# controller.net
KiCad netlist of a schematic drawn in EAGLE
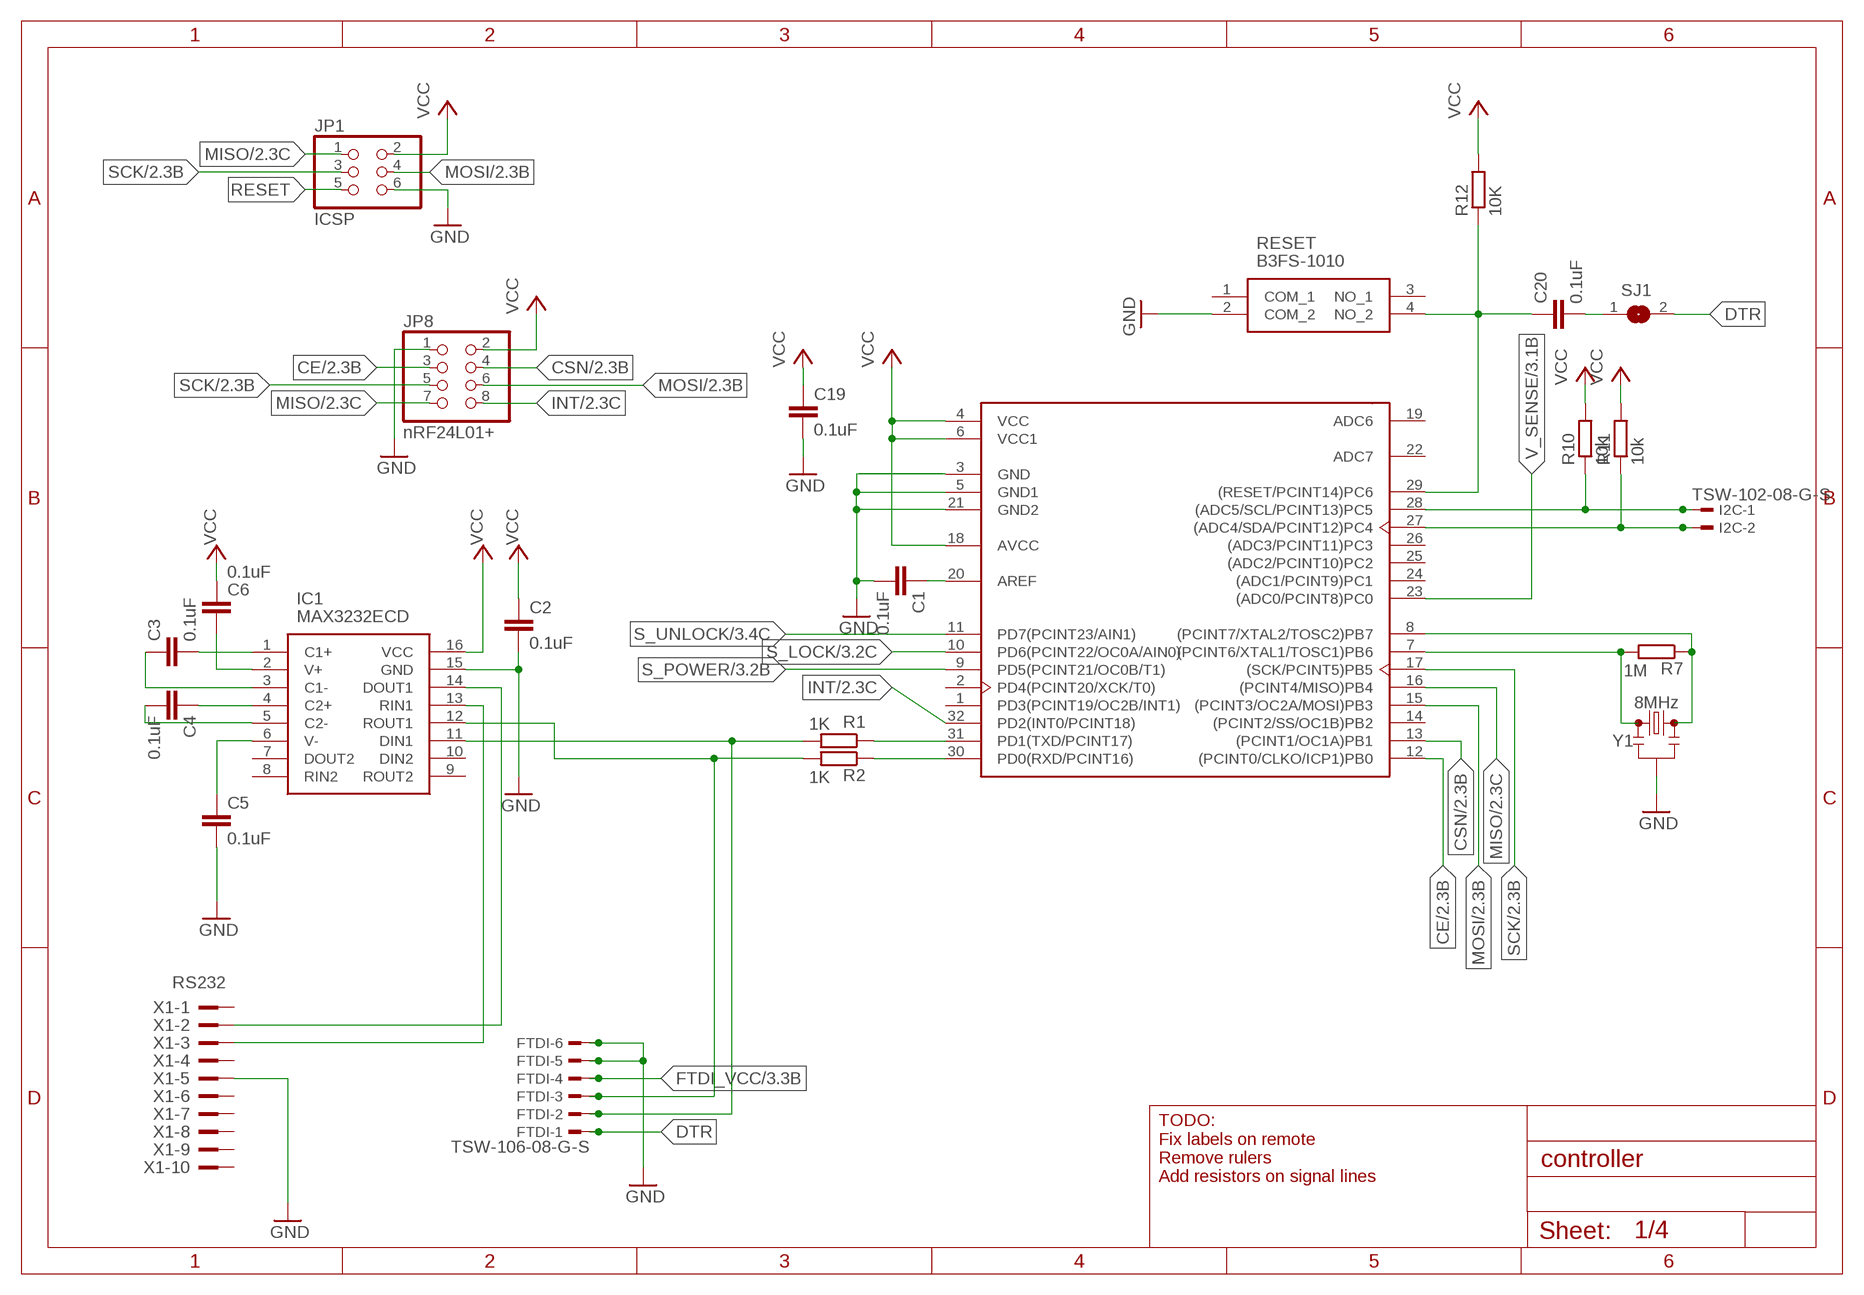
[diagram p0: schematic, sheet 1]
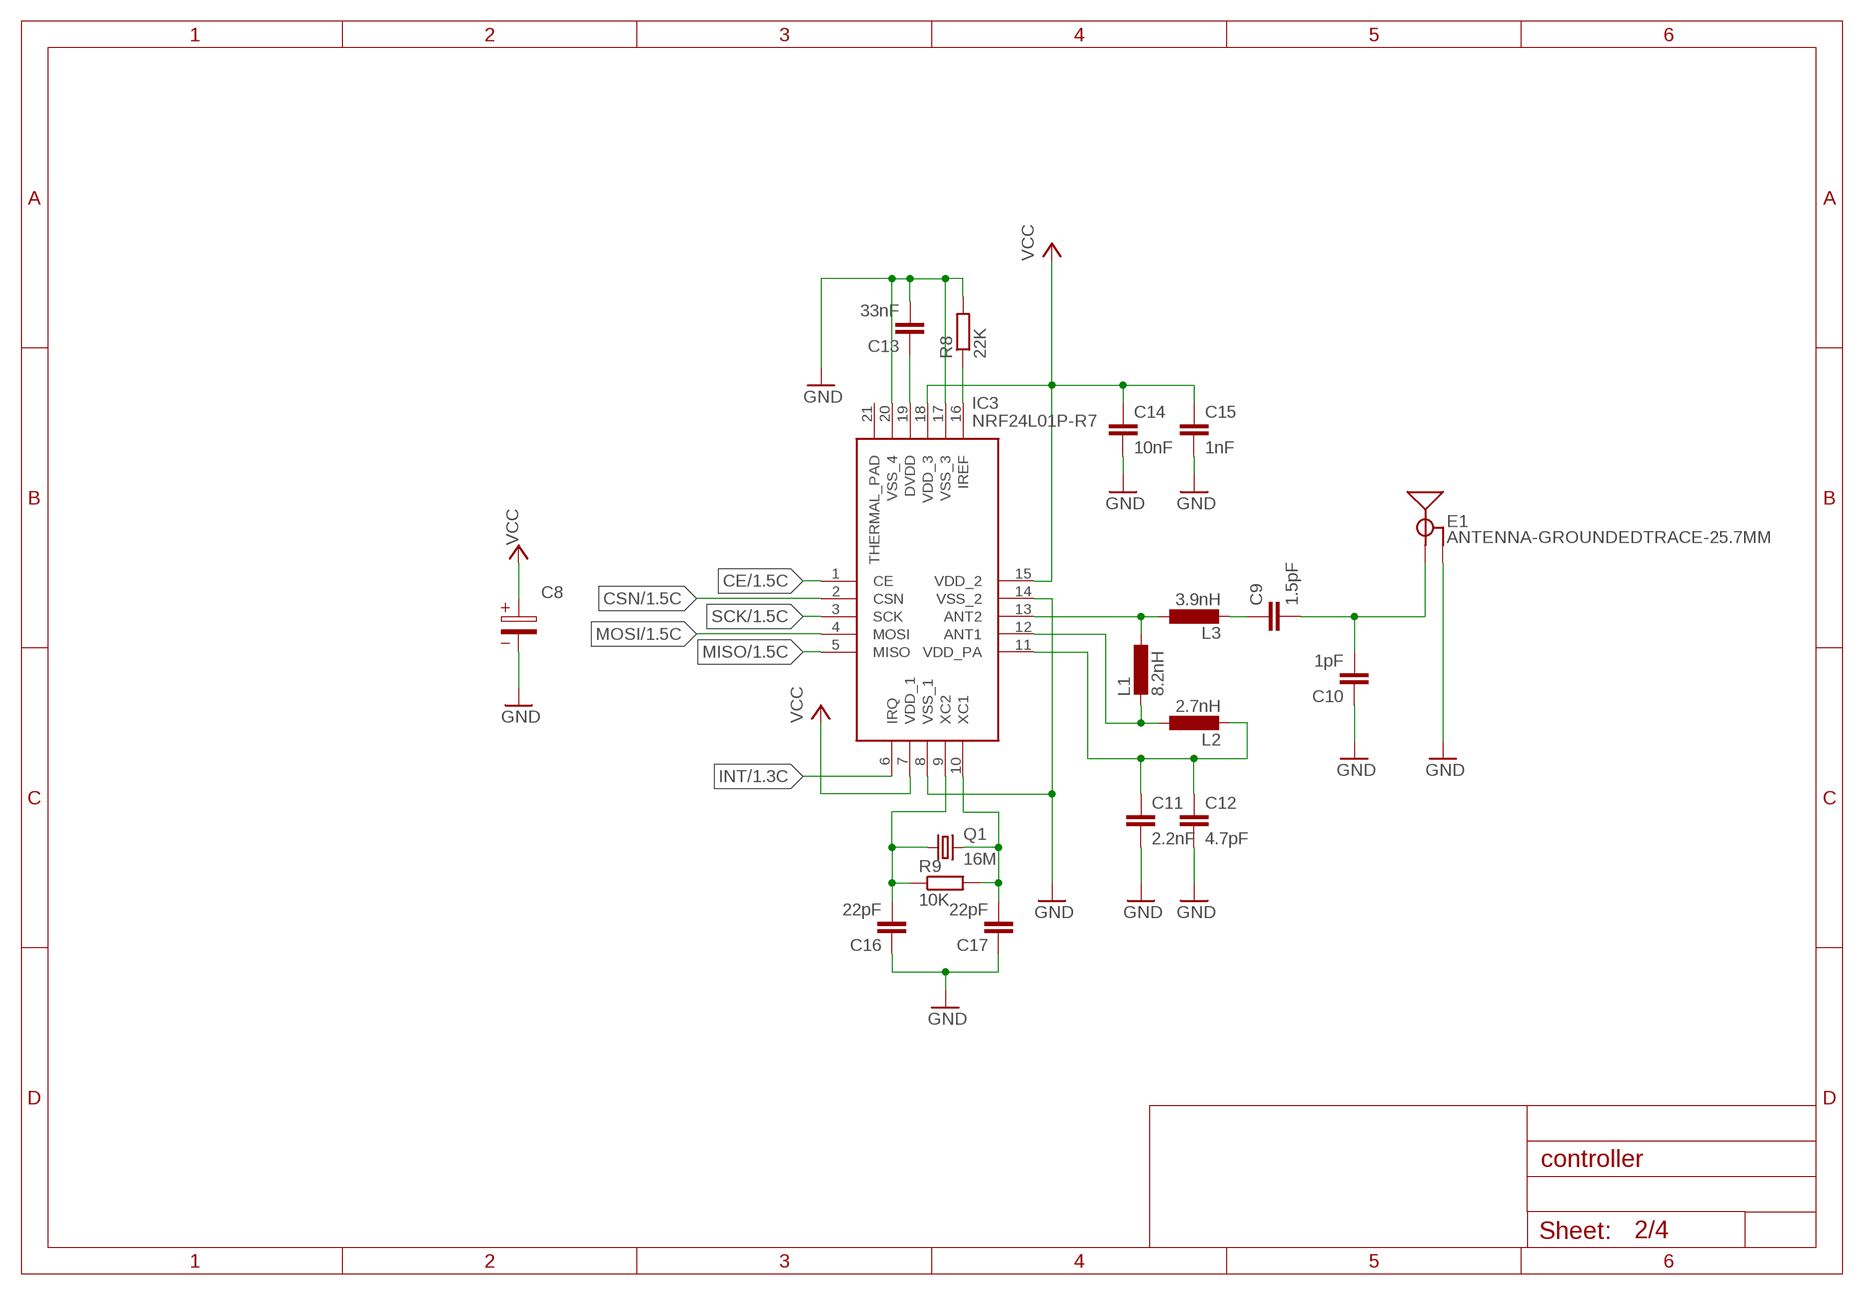
[diagram p1: schematic, sheet 2]
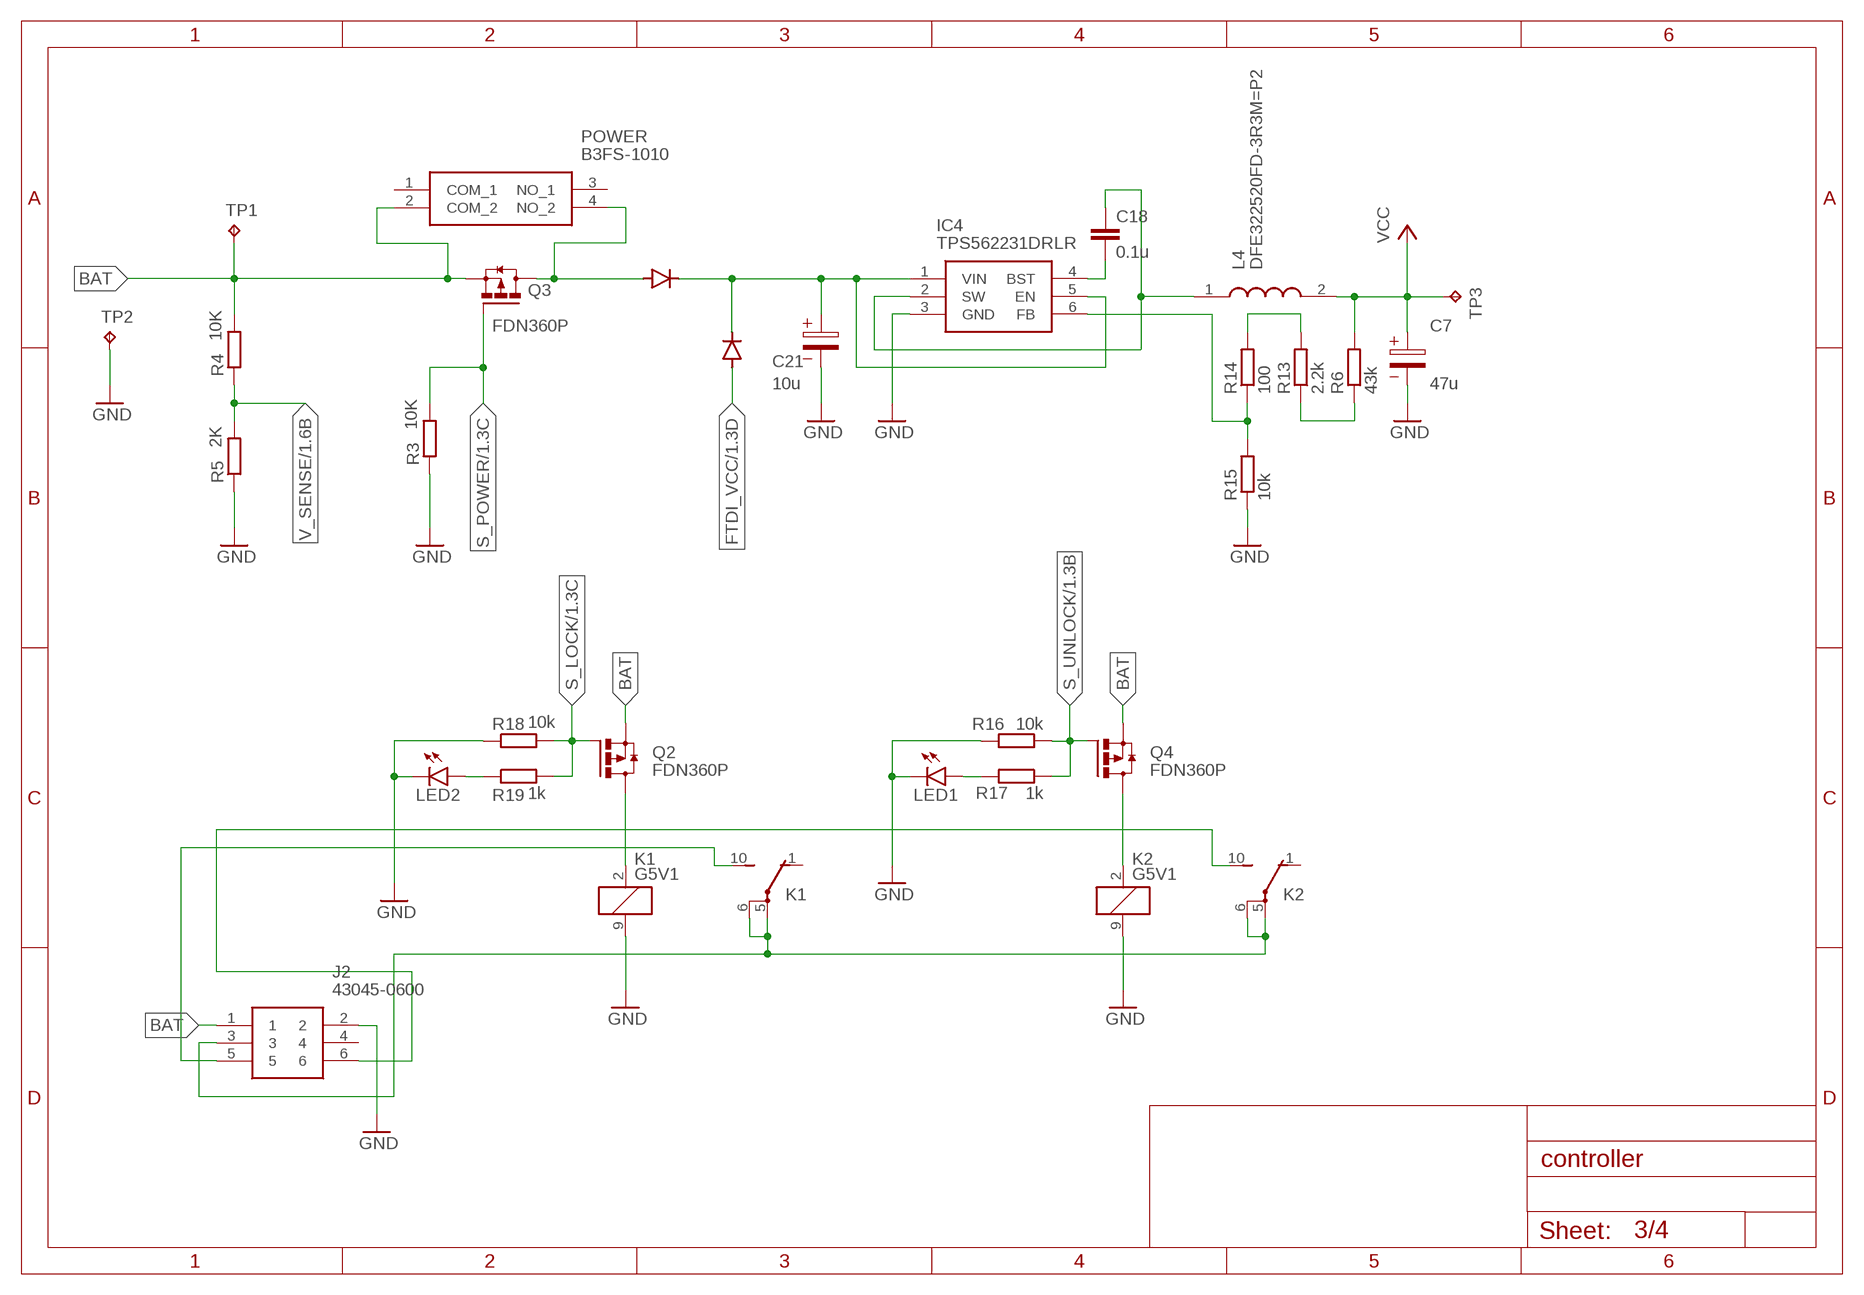
[diagram p2: schematic, sheet 3]
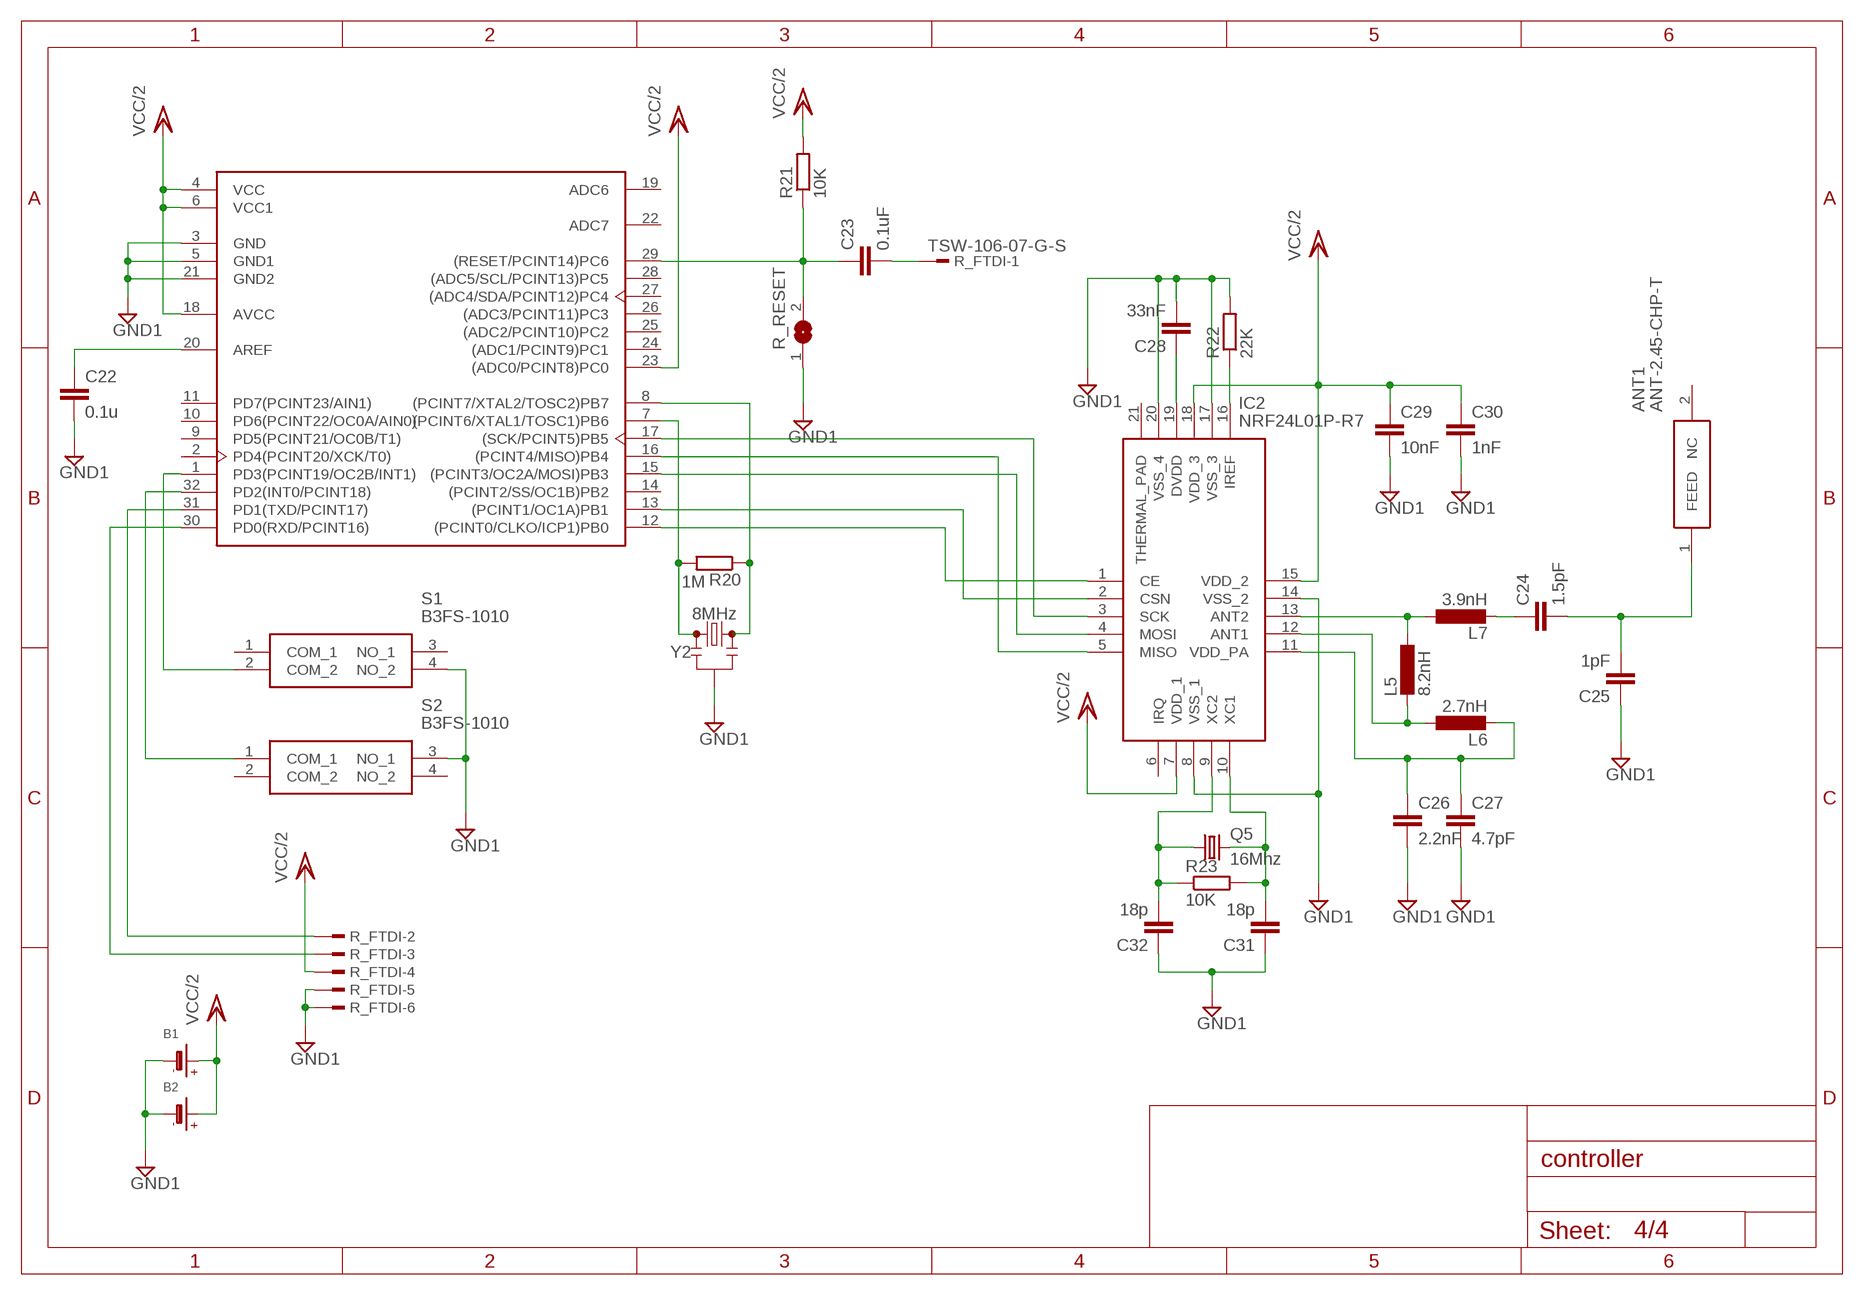
[diagram p3: schematic, sheet 4]

(export (version "E")
  (design (tool "Eeschema 10.0.6"))
  (components
    (comp (ref "C8")
      (value "WCAP-ASLI_8X6,5_865080149011")
      (footprint "eagle-import:4.2X1.9X2.8(BXCXA)")
      (libsource (lib "eagle-import") (part "WCAP-ASLI_865080149011_8X6,5"))
    )
    (comp (ref "C9")
      (value "1.5pF")
      (footprint "eagle-import:C0805")
      (libsource (lib "eagle-import") (part "resistor_348_C-EUC0805"))
    )
    (comp (ref "C10")
      (value "1pF")
      (footprint "eagle-import:C0805")
      (libsource (lib "eagle-import") (part "resistor_348_C-EUC0805"))
    )
    (comp (ref "C11")
      (value "2.2nF")
      (footprint "eagle-import:C0805")
      (libsource (lib "eagle-import") (part "resistor_348_C-EUC0805"))
    )
    (comp (ref "C12")
      (value "4.7pF")
      (footprint "eagle-import:C0805")
      (libsource (lib "eagle-import") (part "resistor_348_C-EUC0805"))
    )
    (comp (ref "C13")
      (value "33nF")
      (footprint "eagle-import:C0805")
      (libsource (lib "eagle-import") (part "resistor_348_C-EUC0805"))
    )
    (comp (ref "C14")
      (value "10nF")
      (footprint "eagle-import:C0805")
      (libsource (lib "eagle-import") (part "resistor_348_C-EUC0805"))
    )
    (comp (ref "C15")
      (value "1nF")
      (footprint "eagle-import:C0805")
      (libsource (lib "eagle-import") (part "resistor_348_C-EUC0805"))
    )
    (comp (ref "C16")
      (value "22pF")
      (footprint "eagle-import:C0805")
      (libsource (lib "eagle-import") (part "resistor_348_C-EUC0805"))
    )
    (comp (ref "C17")
      (value "22pF")
      (footprint "eagle-import:C0805")
      (libsource (lib "eagle-import") (part "resistor_348_C-EUC0805"))
    )
    (comp (ref "E1")
      (value "ANTENNA-GROUNDEDTRACE-25.7MM")
      (footprint "eagle-import:TRACE_ANTENNA_2.4GHZ_25.7MM")
      (libsource (lib "eagle-import") (part "ANTENNA-GROUNDEDTRACE-25.7MM"))
    )
    (comp (ref "IC3")
      (value "NRF24L01P-R7")
      (footprint "eagle-import:QFN50P400X400X95-21N")
      (fields (field (name "MOUSER_PART_NUMBER") "949-NRF24L01P-R7"))
      (libsource (lib "eagle-import") (part "NRF24L01P-R7"))
    )
    (comp (ref "L1")
      (value "8.2nH")
      (footprint "eagle-import:L2012C")
      (libsource (lib "eagle-import") (part "L-EUL2012C"))
    )
    (comp (ref "L2")
      (value "2.7nH")
      (footprint "eagle-import:L2012C")
      (libsource (lib "eagle-import") (part "L-EUL2012C"))
    )
    (comp (ref "L3")
      (value "3.9nH")
      (footprint "eagle-import:L2012C")
      (libsource (lib "eagle-import") (part "L-EUL2012C"))
    )
    (comp (ref "Q1")
      (value "16M")
      (footprint "eagle-import:HC49_S")
      (libsource (lib "eagle-import") (part "CRYSTALHC49S"))
    )
    (comp (ref "R8")
      (value "22K")
      (footprint "eagle-import:R0805")
      (libsource (lib "eagle-import") (part "R-EU_R0805"))
    )
    (comp (ref "R9")
      (value "10K")
      (footprint "eagle-import:R0805")
      (libsource (lib "eagle-import") (part "R-EU_R0805"))
    )
    (comp (ref "C1")
      (value "0.1uF")
      (footprint "eagle-import:C0805")
      (libsource (lib "eagle-import") (part "C-EUC0805"))
    )
    (comp (ref "C2")
      (value "0.1uF")
      (footprint "eagle-import:C0805")
      (libsource (lib "eagle-import") (part "C-EUC0805"))
    )
    (comp (ref "C3")
      (value "0.1uF")
      (footprint "eagle-import:C0805")
      (libsource (lib "eagle-import") (part "C-EUC0805"))
    )
    (comp (ref "C4")
      (value "0.1uF")
      (footprint "eagle-import:C0805")
      (libsource (lib "eagle-import") (part "C-EUC0805"))
    )
    (comp (ref "C5")
      (value "0.1uF")
      (footprint "eagle-import:C0805")
      (libsource (lib "eagle-import") (part "C-EUC0805"))
    )
    (comp (ref "C6")
      (value "0.1uF")
      (footprint "eagle-import:C0805")
      (libsource (lib "eagle-import") (part "C-EUC0805"))
    )
    (comp (ref "C19")
      (value "0.1uF")
      (footprint "eagle-import:C0805")
      (libsource (lib "eagle-import") (part "C-EUC0805"))
    )
    (comp (ref "C20")
      (value "0.1uF")
      (footprint "eagle-import:C0805")
      (libsource (lib "eagle-import") (part "C-EUC0805"))
    )
    (comp (ref "FTDI")
      (value "TSW-106-08-G-S")
      (footprint "eagle-import:TSW-106-XX-G-S")
      (fields (field (name "MF") "Samtec Inc.") (field (name "MPN") "TSW-106-07-G-S"))
      (libsource (lib "eagle-import") (part "TSW-106--G-S08"))
    )
    (comp (ref "I2C")
      (value "TSW-102-08-G-S")
      (footprint "eagle-import:TSW-102-XX-G-S")
      (fields (field (name "MF") "Samtec Inc.") (field (name "MPN") "TSW-102-07-G-S"))
      (libsource (lib "eagle-import") (part "TSW-102--G-S08"))
    )
    (comp (ref "IC1")
      (value "MAX3232ECD")
      (footprint "eagle-import:SOIC127P600X175-16N")
      (fields (field (name "MOUSER_PART_NUMBER") "595-MAX3232ECD") (field (name "RS_PART_NUMBER") "6608704P"))
      (libsource (lib "eagle-import") (part "MAX3232ECD"))
    )
    (comp (ref "JP1")
      (value "ICSP")
      (footprint "eagle-import:2X03")
      (libsource (lib "eagle-import") (part "PINHD-2X3"))
    )
    (comp (ref "JP8")
      (value "nRF24L01+")
      (footprint "eagle-import:2X04")
      (libsource (lib "eagle-import") (part "PINHD-2X4"))
    )
    (comp (ref "R1")
      (value "1K")
      (footprint "eagle-import:R0805")
      (libsource (lib "eagle-import") (part "R-EU_R0805"))
    )
    (comp (ref "R2")
      (value "1K")
      (footprint "eagle-import:R0805")
      (libsource (lib "eagle-import") (part "R-EU_R0805"))
    )
    (comp (ref "R7")
      (value "1M")
      (footprint "eagle-import:R0805")
      (libsource (lib "eagle-import") (part "R-EU_R0805"))
    )
    (comp (ref "R10")
      (value "10k")
      (footprint "eagle-import:R0805")
      (libsource (lib "eagle-import") (part "R-EU_R0805"))
    )
    (comp (ref "R11")
      (value "10k")
      (footprint "eagle-import:R0805")
      (libsource (lib "eagle-import") (part "R-EU_R0805"))
    )
    (comp (ref "R12")
      (value "10K")
      (footprint "eagle-import:R0805")
      (libsource (lib "eagle-import") (part "R-EU_R0805"))
    )
    (comp (ref "RESET")
      (value "B3FS-1010")
      (footprint "eagle-import:B3FS-1000P")
      (fields (field (name "MOUSER_PART_NUMBER") "653-B3FS-1010") (field (name "RS_PART_NUMBER") "6821266P"))
      (libsource (lib "eagle-import") (part "B3FS-1010"))
    )
    (comp (ref "SJ1") (value "SJ") (footprint "eagle-import:SJ") (libsource (lib "eagle-import") (part "SJ")))
    (comp (ref "U2")
      (value "ATMEGA328P-AU")
      (footprint "eagle-import:TQFP-32")
      (fields
        (field (name "DIGIKEY_PART_NUMBER") "ATMEGA328P-AU-ND")
        (field (name "MANUFACTURER") "Microchip Technology")
        (field (name "CREATED_BY") "PCBLayout.com")
      )
      (libsource (lib "eagle-import") (part "ATMEGA328P-AU"))
    )
    (comp (ref "X1")
      (value "RS232")
      (footprint "eagle-import:PAK100_2500-10")
      (fields (field (name "MF") "3M") (field (name "MPN") "2510-6002UB"))
      (libsource (lib "eagle-import") (part "2510-"))
    )
    (comp (ref "Y1")
      (value "8MHz")
      (footprint "eagle-import:RESONATOR-SMD-3.2X1.3")
      (libsource (lib "eagle-import") (part "RESONATOR-8MHZSMD_3.2X1.3"))
    )
    (comp (ref "C7")
      (value "47u")
      (footprint "eagle-import:2.6X1.6X1(BXCXA)")
      (libsource (lib "eagle-import") (part "WCAP-ASLI_865080140004_4X5,5"))
    )
    (comp (ref "C18")
      (value "0.1u")
      (footprint "eagle-import:C0805")
      (libsource (lib "eagle-import") (part "C-EUC0805"))
    )
    (comp (ref "C21")
      (value "10u")
      (footprint "eagle-import:2.6X1.6X1(BXCXA)")
      (libsource (lib "eagle-import") (part "WCAP-ASLI_865080340001_4X5,5"))
    )
    (comp (ref "D1")
      (value "DIODE-SOD123")
      (footprint "eagle-import:SOD123")
      (libsource (lib "eagle-import") (part "DIODE-SOD123"))
    )
    (comp (ref "D2")
      (value "DIODE-SOD123")
      (footprint "eagle-import:SOD123")
      (libsource (lib "eagle-import") (part "DIODE-SOD123"))
    )
    (comp (ref "IC4")
      (value "TPS562231DRLR")
      (footprint "eagle-import:SOTFL50P160X60-6N")
      (fields (field (name "MOUSER_PART_NUMBER") "595-TPS562231DRLR"))
      (libsource (lib "eagle-import") (part "TPS562231DRLR"))
    )
    (comp (ref "J2")
      (value "43045-0600")
      (footprint "eagle-import:43045-0600")
      (fields (field (name "MOUSER_PART_NUMBER") "538-43045-0600") (field (name "RS_PART_NUMBER") "2332961P"))
      (libsource (lib "eagle-import") (part "43045-0600"))
    )
    (comp (ref "K1")
      (value "G5V1")
      (footprint "eagle-import:G5V1")
      (fields (field (name "MPN") "G5V-1-DC24"))
      (libsource (lib "eagle-import") (part "G5V1"))
    )
    (comp (ref "K2")
      (value "G5V1")
      (footprint "eagle-import:G5V1")
      (fields (field (name "MPN") "G5V-1-DC24"))
      (libsource (lib "eagle-import") (part "G5V1"))
    )
    (comp (ref "L4")
      (value "DFE322520FD-3R3M=P2")
      (footprint "eagle-import:INDC3225X200N")
      (fields (field (name "MOUSER_PART_NUMBER") "81-DFE322520FD3R3MP2"))
      (libsource (lib "eagle-import") (part "DFE322520FD-3R3M=P2"))
    )
    (comp (ref "LED1")
      (value "LEDCHIPLED_0805")
      (footprint "eagle-import:CHIPLED_0805")
      (libsource (lib "eagle-import") (part "LEDCHIPLED_0805"))
    )
    (comp (ref "LED2")
      (value "LEDCHIPLED_0805")
      (footprint "eagle-import:CHIPLED_0805")
      (libsource (lib "eagle-import") (part "LEDCHIPLED_0805"))
    )
    (comp (ref "POWER")
      (value "B3FS-1010")
      (footprint "eagle-import:B3FS-1000P")
      (fields (field (name "MOUSER_PART_NUMBER") "653-B3FS-1010") (field (name "RS_PART_NUMBER") "6821266P"))
      (libsource (lib "eagle-import") (part "B3FS-1010"))
    )
    (comp (ref "Q2")
      (value "FDN360P")
      (footprint "eagle-import:SUPER-SOT3")
      (libsource (lib "eagle-import") (part "FDN360P"))
    )
    (comp (ref "Q3")
      (value "FDN360P")
      (footprint "eagle-import:SUPER-SOT3")
      (libsource (lib "eagle-import") (part "FDN360P"))
    )
    (comp (ref "Q4")
      (value "FDN360P")
      (footprint "eagle-import:SUPER-SOT3")
      (libsource (lib "eagle-import") (part "FDN360P"))
    )
    (comp (ref "R3")
      (value "10K")
      (footprint "eagle-import:R0805")
      (libsource (lib "eagle-import") (part "R-EU_R0805"))
    )
    (comp (ref "R4")
      (value "10K")
      (footprint "eagle-import:R0805")
      (libsource (lib "eagle-import") (part "R-EU_R0805"))
    )
    (comp (ref "R5")
      (value "2K")
      (footprint "eagle-import:R0805")
      (libsource (lib "eagle-import") (part "R-EU_R0805"))
    )
    (comp (ref "R6")
      (value "43k")
      (footprint "eagle-import:R0805")
      (libsource (lib "eagle-import") (part "R-EU_R0805"))
    )
    (comp (ref "R13")
      (value "2.2k")
      (footprint "eagle-import:R0805")
      (libsource (lib "eagle-import") (part "R-EU_R0805"))
    )
    (comp (ref "R14")
      (value "100")
      (footprint "eagle-import:R0805")
      (libsource (lib "eagle-import") (part "R-EU_R0805"))
    )
    (comp (ref "R15")
      (value "10k")
      (footprint "eagle-import:R0805")
      (libsource (lib "eagle-import") (part "R-EU_R0805"))
    )
    (comp (ref "R16")
      (value "10k")
      (footprint "eagle-import:R0805")
      (libsource (lib "eagle-import") (part "R-EU_R0805"))
    )
    (comp (ref "R17")
      (value "1k")
      (footprint "eagle-import:R0805")
      (libsource (lib "eagle-import") (part "R-EU_R0805"))
    )
    (comp (ref "R18")
      (value "10k")
      (footprint "eagle-import:R0805")
      (libsource (lib "eagle-import") (part "R-EU_R0805"))
    )
    (comp (ref "R19")
      (value "1k")
      (footprint "eagle-import:R0805")
      (libsource (lib "eagle-import") (part "R-EU_R0805"))
    )
    (comp (ref "TP1")
      (value "TPB1,27")
      (footprint "eagle-import:B1,27")
      (libsource (lib "eagle-import") (part "TPB1,27"))
    )
    (comp (ref "TP2")
      (value "TPB1,27")
      (footprint "eagle-import:B1,27")
      (libsource (lib "eagle-import") (part "TPB1,27"))
    )
    (comp (ref "TP3")
      (value "TPB1,27")
      (footprint "eagle-import:B1,27")
      (libsource (lib "eagle-import") (part "TPB1,27"))
    )
    (comp (ref "ANT1")
      (value "ANT-2.45-CHP-T")
      (footprint "eagle-import:ANT-2.45-CHP-T")
      (fields (field (name "MOUSER_PART_NUMBER") "712-ANT-2.45-CHP-T"))
      (libsource (lib "eagle-import") (part "ANT-2.45-CHP-T"))
    )
    (comp (ref "B1")
      (value "BATTERYCR2032_BAT-HLD-001")
      (footprint "eagle-import:CR2032_SMT_BAT-HLD-001")
      (libsource (lib "eagle-import") (part "BATTERYCR2032_BAT-HLD-001"))
    )
    (comp (ref "B2")
      (value "BATTERYCR2032_BAT-HLD-001")
      (footprint "eagle-import:CR2032_SMT_BAT-HLD-001")
      (libsource (lib "eagle-import") (part "BATTERYCR2032_BAT-HLD-001"))
    )
    (comp (ref "C22")
      (value "0.1u")
      (footprint "eagle-import:C0805")
      (libsource (lib "eagle-import") (part "C-EUC0805"))
    )
    (comp (ref "C23")
      (value "0.1uF")
      (footprint "eagle-import:C0805")
      (libsource (lib "eagle-import") (part "C-EUC0805"))
    )
    (comp (ref "C24")
      (value "1.5pF")
      (footprint "eagle-import:C0805")
      (libsource (lib "eagle-import") (part "resistor_348_C-EUC0805"))
    )
    (comp (ref "C25")
      (value "1pF")
      (footprint "eagle-import:C0805")
      (libsource (lib "eagle-import") (part "resistor_348_C-EUC0805"))
    )
    (comp (ref "C26")
      (value "2.2nF")
      (footprint "eagle-import:C0805")
      (libsource (lib "eagle-import") (part "resistor_348_C-EUC0805"))
    )
    (comp (ref "C27")
      (value "4.7pF")
      (footprint "eagle-import:C0805")
      (libsource (lib "eagle-import") (part "resistor_348_C-EUC0805"))
    )
    (comp (ref "C28")
      (value "33nF")
      (footprint "eagle-import:C0805")
      (libsource (lib "eagle-import") (part "resistor_348_C-EUC0805"))
    )
    (comp (ref "C29")
      (value "10nF")
      (footprint "eagle-import:C0805")
      (libsource (lib "eagle-import") (part "resistor_348_C-EUC0805"))
    )
    (comp (ref "C30")
      (value "1nF")
      (footprint "eagle-import:C0805")
      (libsource (lib "eagle-import") (part "resistor_348_C-EUC0805"))
    )
    (comp (ref "C31")
      (value "18p")
      (footprint "eagle-import:C0805")
      (libsource (lib "eagle-import") (part "resistor_348_C-EUC0805"))
    )
    (comp (ref "C32")
      (value "18p")
      (footprint "eagle-import:C0805")
      (libsource (lib "eagle-import") (part "resistor_348_C-EUC0805"))
    )
    (comp (ref "IC2")
      (value "NRF24L01P-R7")
      (footprint "eagle-import:QFN50P400X400X95-21N")
      (fields (field (name "MOUSER_PART_NUMBER") "949-NRF24L01P-R7"))
      (libsource (lib "eagle-import") (part "NRF24L01P-R7"))
    )
    (comp (ref "L5")
      (value "8.2nH")
      (footprint "eagle-import:L2012C")
      (libsource (lib "eagle-import") (part "L-EUL2012C"))
    )
    (comp (ref "L6")
      (value "2.7nH")
      (footprint "eagle-import:L2012C")
      (libsource (lib "eagle-import") (part "L-EUL2012C"))
    )
    (comp (ref "L7")
      (value "3.9nH")
      (footprint "eagle-import:L2012C")
      (libsource (lib "eagle-import") (part "L-EUL2012C"))
    )
    (comp (ref "Q5")
      (value "16Mhz")
      (footprint "eagle-import:HC49UP")
      (libsource (lib "eagle-import") (part "CRYSTALHC49UP"))
    )
    (comp (ref "R20")
      (value "1M")
      (footprint "eagle-import:R0805")
      (libsource (lib "eagle-import") (part "R-EU_R0805"))
    )
    (comp (ref "R21")
      (value "10K")
      (footprint "eagle-import:R0805")
      (libsource (lib "eagle-import") (part "R-EU_R0805"))
    )
    (comp (ref "R22")
      (value "22K")
      (footprint "eagle-import:R0805")
      (libsource (lib "eagle-import") (part "R-EU_R0805"))
    )
    (comp (ref "R23")
      (value "10K")
      (footprint "eagle-import:R0805")
      (libsource (lib "eagle-import") (part "R-EU_R0805"))
    )
    (comp (ref "R_FTDI")
      (value "TSW-106-07-G-S")
      (footprint "eagle-import:TSW-106-XX-G-S")
      (fields (field (name "MF") "Samtec Inc."))
      (libsource (lib "eagle-import") (part "TSW-106--G-S07"))
    )
    (comp (ref "R_RESET")
      (value "SJ")
      (footprint "eagle-import:SJ")
      (libsource (lib "eagle-import") (part "SJ"))
    )
    (comp (ref "S1")
      (value "B3FS-1010")
      (footprint "eagle-import:B3FS-1000P")
      (fields (field (name "MOUSER_PART_NUMBER") "653-B3FS-1010") (field (name "RS_PART_NUMBER") "6821266P"))
      (libsource (lib "eagle-import") (part "B3FS-1010"))
    )
    (comp (ref "S2")
      (value "B3FS-1010")
      (footprint "eagle-import:B3FS-1000P")
      (fields (field (name "MOUSER_PART_NUMBER") "653-B3FS-1010") (field (name "RS_PART_NUMBER") "6821266P"))
      (libsource (lib "eagle-import") (part "B3FS-1010"))
    )
    (comp (ref "U1")
      (value "ATMEGA328P-AU")
      (footprint "eagle-import:TQFP-32")
      (fields
        (field (name "DIGIKEY_PART_NUMBER") "ATMEGA328P-AU-ND")
        (field (name "MANUFACTURER") "Microchip Technology")
        (field (name "CREATED_BY") "PCBLayout.com")
      )
      (libsource (lib "eagle-import") (part "ATMEGA328P-AU"))
    )
    (comp (ref "Y2")
      (value "8MHz")
      (footprint "eagle-import:RESONATOR-SMD-3.2X1.3")
      (libsource (lib "eagle-import") (part "RESONATOR-8MHZSMD_3.2X1.3"))
    )
  )
  (nets
    (net (code "1") (name "BAT") (class "Default")
      (node (ref "J2") (pin "1") (pinfunction "1_1") (pintype "bidirectional"))
      (node (ref "POWER") (pin "2") (pinfunction "COM_2_2") (pintype "bidirectional"))
      (node (ref "Q2") (pin "2") (pinfunction "S_2") (pintype "passive"))
      (node (ref "Q3") (pin "2") (pinfunction "S_2") (pintype "passive"))
      (node (ref "Q4") (pin "2") (pinfunction "S_2") (pintype "passive"))
      (node (ref "R4") (pin "2") (pinfunction "2_2") (pintype "passive"))
      (node (ref "TP1") (pin "TP") (pinfunction "TP_TP") (pintype "input"))
    )
    (net (code "2") (name "CE") (class "Default")
      (node (ref "IC3") (pin "1") (pinfunction "CE_1") (pintype "bidirectional"))
      (node (ref "JP8") (pin "3") (pinfunction "3_3") (pintype "passive"))
      (node (ref "U2") (pin "12") (pinfunction "(PCINT0/CLKO/ICP1)PB0_12") (pintype "bidirectional"))
    )
    (net (code "3") (name "CSN") (class "Default")
      (node (ref "IC3") (pin "2") (pinfunction "CSN_2") (pintype "bidirectional"))
      (node (ref "JP8") (pin "4") (pinfunction "4_4") (pintype "passive"))
      (node (ref "U2") (pin "13") (pinfunction "(PCINT1/OC1A)PB1_13") (pintype "bidirectional"))
    )
    (net (code "4") (name "DTR") (class "Default")
      (node (ref "FTDI") (pin "1") (pinfunction "1_1") (pintype "passive"))
      (node (ref "SJ1") (pin "2") (pinfunction "2_2") (pintype "passive"))
    )
    (net (code "5") (name "FTDI_VCC") (class "Default")
      (node (ref "D1") (pin "A") (pinfunction "A_A") (pintype "passive"))
      (node (ref "FTDI") (pin "4") (pinfunction "1_4") (pintype "passive"))
    )
    (net (code "6") (name "GND") (class "Default")
      (node (ref "C1") (pin "2") (pinfunction "2_2") (pintype "passive"))
      (node (ref "C10") (pin "1") (pinfunction "1_1") (pintype "passive"))
      (node (ref "C11") (pin "2") (pinfunction "2_2") (pintype "passive"))
      (node (ref "C12") (pin "2") (pinfunction "2_2") (pintype "passive"))
      (node (ref "C13") (pin "2") (pinfunction "2_2") (pintype "passive"))
      (node (ref "C14") (pin "2") (pinfunction "2_2") (pintype "passive"))
      (node (ref "C15") (pin "2") (pinfunction "2_2") (pintype "passive"))
      (node (ref "C16") (pin "1") (pinfunction "1_1") (pintype "passive"))
      (node (ref "C17") (pin "1") (pinfunction "1_1") (pintype "passive"))
      (node (ref "C19") (pin "2") (pinfunction "2_2") (pintype "passive"))
      (node (ref "C2") (pin "2") (pinfunction "2_2") (pintype "passive"))
      (node (ref "C21") (pin "2") (pinfunction "2_2") (pintype "passive"))
      (node (ref "C5") (pin "2") (pinfunction "2_2") (pintype "passive"))
      (node (ref "C7") (pin "2") (pinfunction "2_2") (pintype "passive"))
      (node (ref "C8") (pin "2") (pinfunction "2_2") (pintype "passive"))
      (node (ref "E1") (pin "GND") (pinfunction "GND_GND") (pintype "bidirectional"))
      (node (ref "E1") (pin "GND2") (pinfunction "GND_GND2") (pintype "bidirectional"))
      (node (ref "FTDI") (pin "5") (pinfunction "1_5") (pintype "passive"))
      (node (ref "FTDI") (pin "6") (pinfunction "1_6") (pintype "passive"))
      (node (ref "IC1") (pin "15") (pinfunction "GND_15") (pintype "bidirectional"))
      (node (ref "IC3") (pin "14") (pinfunction "VSS_2_14") (pintype "bidirectional"))
      (node (ref "IC3") (pin "17") (pinfunction "VSS_3_17") (pintype "bidirectional"))
      (node (ref "IC3") (pin "20") (pinfunction "VSS_4_20") (pintype "bidirectional"))
      (node (ref "IC3") (pin "8") (pinfunction "VSS_1_8") (pintype "bidirectional"))
      (node (ref "IC4") (pin "3") (pinfunction "GND_3") (pintype "bidirectional"))
      (node (ref "J2") (pin "2") (pinfunction "2_2") (pintype "bidirectional"))
      (node (ref "JP1") (pin "6") (pinfunction "6_6") (pintype "passive"))
      (node (ref "JP8") (pin "1") (pinfunction "1_1") (pintype "passive"))
      (node (ref "K1") (pin "9") (pinfunction "2_9") (pintype "passive"))
      (node (ref "K2") (pin "9") (pinfunction "2_9") (pintype "passive"))
      (node (ref "LED1") (pin "C") (pinfunction "C_C") (pintype "passive"))
      (node (ref "LED2") (pin "C") (pinfunction "C_C") (pintype "passive"))
      (node (ref "R15") (pin "1") (pinfunction "1_1") (pintype "passive"))
      (node (ref "R16") (pin "2") (pinfunction "2_2") (pintype "passive"))
      (node (ref "R18") (pin "1") (pinfunction "1_1") (pintype "passive"))
      (node (ref "R3") (pin "1") (pinfunction "1_1") (pintype "passive"))
      (node (ref "R5") (pin "1") (pinfunction "1_1") (pintype "passive"))
      (node (ref "R8") (pin "2") (pinfunction "2_2") (pintype "passive"))
      (node (ref "RESET") (pin "2") (pinfunction "COM_2_2") (pintype "bidirectional"))
      (node (ref "TP2") (pin "TP") (pinfunction "TP_TP") (pintype "input"))
      (node (ref "U2") (pin "21") (pinfunction "GND2_21") (pintype "power_in"))
      (node (ref "U2") (pin "3") (pinfunction "GND_3") (pintype "power_in"))
      (node (ref "U2") (pin "5") (pinfunction "GND1_5") (pintype "power_in"))
      (node (ref "X1") (pin "5") (pinfunction "KL_5") (pintype "passive"))
      (node (ref "Y1") (pin "2") (pinfunction "2_2") (pintype "passive"))
    )
    (net (code "7") (name "GND1") (class "Default")
      (node (ref "B1") (pin "-") (pinfunction "-_-") (pintype "passive"))
      (node (ref "B2") (pin "-") (pinfunction "-_-") (pintype "passive"))
      (node (ref "C22") (pin "2") (pinfunction "2_2") (pintype "passive"))
      (node (ref "C25") (pin "1") (pinfunction "1_1") (pintype "passive"))
      (node (ref "C26") (pin "2") (pinfunction "2_2") (pintype "passive"))
      (node (ref "C27") (pin "2") (pinfunction "2_2") (pintype "passive"))
      (node (ref "C28") (pin "2") (pinfunction "2_2") (pintype "passive"))
      (node (ref "C29") (pin "2") (pinfunction "2_2") (pintype "passive"))
      (node (ref "C30") (pin "2") (pinfunction "2_2") (pintype "passive"))
      (node (ref "C31") (pin "1") (pinfunction "1_1") (pintype "passive"))
      (node (ref "C32") (pin "1") (pinfunction "1_1") (pintype "passive"))
      (node (ref "IC2") (pin "14") (pinfunction "VSS_2_14") (pintype "bidirectional"))
      (node (ref "IC2") (pin "17") (pinfunction "VSS_3_17") (pintype "bidirectional"))
      (node (ref "IC2") (pin "20") (pinfunction "VSS_4_20") (pintype "bidirectional"))
      (node (ref "IC2") (pin "8") (pinfunction "VSS_1_8") (pintype "bidirectional"))
      (node (ref "R22") (pin "2") (pinfunction "2_2") (pintype "passive"))
      (node (ref "R_FTDI") (pin "5") (pinfunction "1_5") (pintype "passive"))
      (node (ref "R_FTDI") (pin "6") (pinfunction "1_6") (pintype "passive"))
      (node (ref "R_RESET") (pin "1") (pinfunction "1_1") (pintype "passive"))
      (node (ref "S1") (pin "4") (pinfunction "NO_2_4") (pintype "bidirectional"))
      (node (ref "S2") (pin "3") (pinfunction "NO_1_3") (pintype "bidirectional"))
      (node (ref "U1") (pin "21") (pinfunction "GND2_21") (pintype "power_in"))
      (node (ref "U1") (pin "3") (pinfunction "GND_3") (pintype "power_in"))
      (node (ref "U1") (pin "5") (pinfunction "GND1_5") (pintype "power_in"))
      (node (ref "Y2") (pin "2") (pinfunction "2_2") (pintype "passive"))
    )
    (net (code "8") (name "INT") (class "Default")
      (node (ref "IC3") (pin "6") (pinfunction "IRQ_6") (pintype "bidirectional"))
      (node (ref "JP8") (pin "8") (pinfunction "8_8") (pintype "passive"))
      (node (ref "U2") (pin "32") (pinfunction "PD2(INT0/PCINT18)_32") (pintype "bidirectional"))
    )
    (net (code "9") (name "MISO") (class "Default")
      (node (ref "IC3") (pin "5") (pinfunction "MISO_5") (pintype "bidirectional"))
      (node (ref "JP1") (pin "1") (pinfunction "1_1") (pintype "passive"))
      (node (ref "JP8") (pin "7") (pinfunction "7_7") (pintype "passive"))
      (node (ref "U2") (pin "16") (pinfunction "(PCINT4/MISO)PB4_16") (pintype "bidirectional"))
    )
    (net (code "10") (name "MOSI") (class "Default")
      (node (ref "IC3") (pin "4") (pinfunction "MOSI_4") (pintype "bidirectional"))
      (node (ref "JP1") (pin "4") (pinfunction "4_4") (pintype "passive"))
      (node (ref "JP8") (pin "6") (pinfunction "6_6") (pintype "passive"))
      (node (ref "U2") (pin "15") (pinfunction "(PCINT3/OC2A/MOSI)PB3_15") (pintype "bidirectional"))
    )
    (net (code "11") (name "Net-(ANT1-FEED)") (class "Default")
      (node (ref "ANT1") (pin "1") (pinfunction "FEED_1") (pintype "input"))
      (node (ref "C24") (pin "2") (pinfunction "2_2") (pintype "passive"))
      (node (ref "C25") (pin "2") (pinfunction "2_2") (pintype "passive"))
    )
    (net (code "12") (name "Net-(C9-Pad1)") (class "Default")
      (node (ref "C9") (pin "1") (pinfunction "1_1") (pintype "passive"))
      (node (ref "L3") (pin "2") (pinfunction "2_2") (pintype "passive"))
    )
    (net (code "13") (name "Net-(C20-Pad2)") (class "Default")
      (node (ref "C20") (pin "2") (pinfunction "2_2") (pintype "passive"))
      (node (ref "SJ1") (pin "1") (pinfunction "1_1") (pintype "passive"))
    )
    (net (code "14") (name "Net-(C23-Pad2)") (class "Default")
      (node (ref "C23") (pin "2") (pinfunction "2_2") (pintype "passive"))
      (node (ref "R_FTDI") (pin "1") (pinfunction "1_1") (pintype "passive"))
    )
    (net (code "15") (name "Net-(C24-Pad1)") (class "Default")
      (node (ref "C24") (pin "1") (pinfunction "1_1") (pintype "passive"))
      (node (ref "L7") (pin "2") (pinfunction "2_2") (pintype "passive"))
    )
    (net (code "16") (name "Net-(E1-SIGNAL)") (class "Default")
      (node (ref "C10") (pin "2") (pinfunction "2_2") (pintype "passive"))
      (node (ref "C9") (pin "2") (pinfunction "2_2") (pintype "passive"))
      (node (ref "E1") (pin "ANT") (pinfunction "SIGNAL_ANT") (pintype "bidirectional"))
    )
    (net (code "17") (name "Net-(FTDIB-1)") (class "Default")
      (node (ref "FTDI") (pin "2") (pinfunction "1_2") (pintype "passive"))
      (node (ref "IC1") (pin "11") (pinfunction "DIN1_11") (pintype "bidirectional"))
      (node (ref "R1") (pin "2") (pinfunction "2_2") (pintype "passive"))
    )
    (net (code "18") (name "Net-(FTDIC-1)") (class "Default")
      (node (ref "FTDI") (pin "3") (pinfunction "1_3") (pintype "passive"))
      (node (ref "IC1") (pin "12") (pinfunction "ROUT1_12") (pintype "bidirectional"))
      (node (ref "R2") (pin "2") (pinfunction "2_2") (pintype "passive"))
    )
    (net (code "19") (name "Net-(I2CB-1)") (class "Default")
      (node (ref "I2C") (pin "2") (pinfunction "1_2") (pintype "passive"))
      (node (ref "R11") (pin "1") (pinfunction "1_1") (pintype "passive"))
      (node (ref "U2") (pin "27") (pinfunction "(ADC4/SDA/PCINT12)PC4_27") (pintype "bidirectional"))
    )
    (net (code "20") (name "Net-(IC1-C1+)") (class "Default")
      (node (ref "C3") (pin "2") (pinfunction "2_2") (pintype "passive"))
      (node (ref "IC1") (pin "1") (pinfunction "C1+_1") (pintype "bidirectional"))
    )
    (net (code "21") (name "Net-(IC1-C1-)") (class "Default")
      (node (ref "C3") (pin "1") (pinfunction "1_1") (pintype "passive"))
      (node (ref "IC1") (pin "3") (pinfunction "C1-_3") (pintype "bidirectional"))
    )
    (net (code "22") (name "Net-(IC1-C2+)") (class "Default")
      (node (ref "C4") (pin "1") (pinfunction "1_1") (pintype "passive"))
      (node (ref "IC1") (pin "4") (pinfunction "C2+_4") (pintype "bidirectional"))
    )
    (net (code "23") (name "Net-(IC1-C2-)") (class "Default")
      (node (ref "C4") (pin "2") (pinfunction "2_2") (pintype "passive"))
      (node (ref "IC1") (pin "5") (pinfunction "C2-_5") (pintype "bidirectional"))
    )
    (net (code "24") (name "Net-(IC1-DOUT1)") (class "Default")
      (node (ref "IC1") (pin "14") (pinfunction "DOUT1_14") (pintype "bidirectional"))
      (node (ref "X1") (pin "2") (pinfunction "KL_2") (pintype "passive"))
    )
    (net (code "25") (name "Net-(IC1-RIN1)") (class "Default")
      (node (ref "IC1") (pin "13") (pinfunction "RIN1_13") (pintype "bidirectional"))
      (node (ref "X1") (pin "3") (pinfunction "KL_3") (pintype "passive"))
    )
    (net (code "26") (name "Net-(IC1-V+)") (class "Default")
      (node (ref "C6") (pin "1") (pinfunction "1_1") (pintype "passive"))
      (node (ref "IC1") (pin "2") (pinfunction "V+_2") (pintype "bidirectional"))
    )
    (net (code "27") (name "Net-(IC1-V-)") (class "Default")
      (node (ref "C5") (pin "1") (pinfunction "1_1") (pintype "passive"))
      (node (ref "IC1") (pin "6") (pinfunction "V-_6") (pintype "bidirectional"))
    )
    (net (code "28") (name "Net-(IC2-ANT1)") (class "Default")
      (node (ref "IC2") (pin "12") (pinfunction "ANT1_12") (pintype "bidirectional"))
      (node (ref "L5") (pin "2") (pinfunction "2_2") (pintype "passive"))
      (node (ref "L6") (pin "1") (pinfunction "1_1") (pintype "passive"))
    )
    (net (code "29") (name "Net-(IC2-ANT2)") (class "Default")
      (node (ref "IC2") (pin "13") (pinfunction "ANT2_13") (pintype "bidirectional"))
      (node (ref "L5") (pin "1") (pinfunction "1_1") (pintype "passive"))
      (node (ref "L7") (pin "1") (pinfunction "1_1") (pintype "passive"))
    )
    (net (code "30") (name "Net-(IC2-CE)") (class "Default")
      (node (ref "IC2") (pin "1") (pinfunction "CE_1") (pintype "bidirectional"))
      (node (ref "U1") (pin "12") (pinfunction "(PCINT0/CLKO/ICP1)PB0_12") (pintype "bidirectional"))
    )
    (net (code "31") (name "Net-(IC2-CSN)") (class "Default")
      (node (ref "IC2") (pin "2") (pinfunction "CSN_2") (pintype "bidirectional"))
      (node (ref "U1") (pin "13") (pinfunction "(PCINT1/OC1A)PB1_13") (pintype "bidirectional"))
    )
    (net (code "32") (name "Net-(IC2-DVDD)") (class "Default")
      (node (ref "C28") (pin "1") (pinfunction "1_1") (pintype "passive"))
      (node (ref "IC2") (pin "19") (pinfunction "DVDD_19") (pintype "bidirectional"))
    )
    (net (code "33") (name "Net-(IC2-IREF)") (class "Default")
      (node (ref "IC2") (pin "16") (pinfunction "IREF_16") (pintype "bidirectional"))
      (node (ref "R22") (pin "1") (pinfunction "1_1") (pintype "passive"))
    )
    (net (code "34") (name "Net-(IC2-MISO)") (class "Default")
      (node (ref "IC2") (pin "5") (pinfunction "MISO_5") (pintype "bidirectional"))
      (node (ref "U1") (pin "16") (pinfunction "(PCINT4/MISO)PB4_16") (pintype "bidirectional"))
    )
    (net (code "35") (name "Net-(IC2-MOSI)") (class "Default")
      (node (ref "IC2") (pin "4") (pinfunction "MOSI_4") (pintype "bidirectional"))
      (node (ref "U1") (pin "15") (pinfunction "(PCINT3/OC2A/MOSI)PB3_15") (pintype "bidirectional"))
    )
    (net (code "36") (name "Net-(IC2-SCK)") (class "Default")
      (node (ref "IC2") (pin "3") (pinfunction "SCK_3") (pintype "bidirectional"))
      (node (ref "U1") (pin "17") (pinfunction "(SCK/PCINT5)PB5_17") (pintype "bidirectional"))
    )
    (net (code "37") (name "Net-(IC2-VDD_PA)") (class "Default")
      (node (ref "C26") (pin "1") (pinfunction "1_1") (pintype "passive"))
      (node (ref "C27") (pin "1") (pinfunction "1_1") (pintype "passive"))
      (node (ref "IC2") (pin "11") (pinfunction "VDD_PA_11") (pintype "bidirectional"))
      (node (ref "L6") (pin "2") (pinfunction "2_2") (pintype "passive"))
    )
    (net (code "38") (name "Net-(IC2-XC1)") (class "Default")
      (node (ref "C31") (pin "2") (pinfunction "2_2") (pintype "passive"))
      (node (ref "IC2") (pin "10") (pinfunction "XC1_10") (pintype "bidirectional"))
      (node (ref "Q5") (pin "2") (pinfunction "2_2") (pintype "passive"))
      (node (ref "R23") (pin "2") (pinfunction "2_2") (pintype "passive"))
    )
    (net (code "39") (name "Net-(IC2-XC2)") (class "Default")
      (node (ref "C32") (pin "2") (pinfunction "2_2") (pintype "passive"))
      (node (ref "IC2") (pin "9") (pinfunction "XC2_9") (pintype "bidirectional"))
      (node (ref "Q5") (pin "1") (pinfunction "1_1") (pintype "passive"))
      (node (ref "R23") (pin "1") (pinfunction "1_1") (pintype "passive"))
    )
    (net (code "40") (name "Net-(IC3-ANT1)") (class "Default")
      (node (ref "IC3") (pin "12") (pinfunction "ANT1_12") (pintype "bidirectional"))
      (node (ref "L1") (pin "2") (pinfunction "2_2") (pintype "passive"))
      (node (ref "L2") (pin "1") (pinfunction "1_1") (pintype "passive"))
    )
    (net (code "41") (name "Net-(IC3-ANT2)") (class "Default")
      (node (ref "IC3") (pin "13") (pinfunction "ANT2_13") (pintype "bidirectional"))
      (node (ref "L1") (pin "1") (pinfunction "1_1") (pintype "passive"))
      (node (ref "L3") (pin "1") (pinfunction "1_1") (pintype "passive"))
    )
    (net (code "42") (name "Net-(IC3-DVDD)") (class "Default")
      (node (ref "C13") (pin "1") (pinfunction "1_1") (pintype "passive"))
      (node (ref "IC3") (pin "19") (pinfunction "DVDD_19") (pintype "bidirectional"))
    )
    (net (code "43") (name "Net-(IC3-IREF)") (class "Default")
      (node (ref "IC3") (pin "16") (pinfunction "IREF_16") (pintype "bidirectional"))
      (node (ref "R8") (pin "1") (pinfunction "1_1") (pintype "passive"))
    )
    (net (code "44") (name "Net-(IC3-VDD_PA)") (class "Default")
      (node (ref "C11") (pin "1") (pinfunction "1_1") (pintype "passive"))
      (node (ref "C12") (pin "1") (pinfunction "1_1") (pintype "passive"))
      (node (ref "IC3") (pin "11") (pinfunction "VDD_PA_11") (pintype "bidirectional"))
      (node (ref "L2") (pin "2") (pinfunction "2_2") (pintype "passive"))
    )
    (net (code "45") (name "Net-(IC3-XC1)") (class "Default")
      (node (ref "C17") (pin "2") (pinfunction "2_2") (pintype "passive"))
      (node (ref "IC3") (pin "10") (pinfunction "XC1_10") (pintype "bidirectional"))
      (node (ref "Q1") (pin "2") (pinfunction "2_2") (pintype "passive"))
      (node (ref "R9") (pin "2") (pinfunction "2_2") (pintype "passive"))
    )
    (net (code "46") (name "Net-(IC3-XC2)") (class "Default")
      (node (ref "C16") (pin "2") (pinfunction "2_2") (pintype "passive"))
      (node (ref "IC3") (pin "9") (pinfunction "XC2_9") (pintype "bidirectional"))
      (node (ref "Q1") (pin "1") (pinfunction "1_1") (pintype "passive"))
      (node (ref "R9") (pin "1") (pinfunction "1_1") (pintype "passive"))
    )
    (net (code "47") (name "Net-(IC4-BST)") (class "Default")
      (node (ref "C18") (pin "2") (pinfunction "2_2") (pintype "passive"))
      (node (ref "IC4") (pin "4") (pinfunction "BST_4") (pintype "bidirectional"))
    )
    (net (code "48") (name "Net-(IC4-EN)") (class "Default")
      (node (ref "C21") (pin "1") (pinfunction "1_1") (pintype "passive"))
      (node (ref "D1") (pin "C") (pinfunction "C_C") (pintype "passive"))
      (node (ref "D2") (pin "C") (pinfunction "C_C") (pintype "passive"))
      (node (ref "IC4") (pin "1") (pinfunction "VIN_1") (pintype "bidirectional"))
      (node (ref "IC4") (pin "5") (pinfunction "EN_5") (pintype "bidirectional"))
    )
    (net (code "49") (name "Net-(IC4-FB)") (class "Default")
      (node (ref "IC4") (pin "6") (pinfunction "FB_6") (pintype "bidirectional"))
      (node (ref "R14") (pin "1") (pinfunction "1_1") (pintype "passive"))
      (node (ref "R15") (pin "2") (pinfunction "2_2") (pintype "passive"))
    )
    (net (code "50") (name "Net-(IC4-SW)") (class "Default")
      (node (ref "C18") (pin "1") (pinfunction "1_1") (pintype "passive"))
      (node (ref "IC4") (pin "2") (pinfunction "SW_2") (pintype "bidirectional"))
      (node (ref "L4") (pin "1") (pinfunction "1_1") (pintype "bidirectional"))
    )
    (net (code "51") (name "Net-(J2-Pad3)") (class "Default")
      (node (ref "J2") (pin "3") (pinfunction "3_3") (pintype "bidirectional"))
      (node (ref "K1") (pin "5") (pinfunction "P_5") (pintype "passive"))
      (node (ref "K1") (pin "6") (pinfunction "P_6") (pintype "passive"))
      (node (ref "K2") (pin "5") (pinfunction "P_5") (pintype "passive"))
      (node (ref "K2") (pin "6") (pinfunction "P_6") (pintype "passive"))
    )
    (net (code "52") (name "Net-(K1A-1)") (class "Default")
      (node (ref "K1") (pin "2") (pinfunction "1_2") (pintype "passive"))
      (node (ref "Q2") (pin "3") (pinfunction "D_3") (pintype "passive"))
    )
    (net (code "53") (name "Net-(K1B-S)") (class "Default")
      (node (ref "J2") (pin "5") (pinfunction "5_5") (pintype "bidirectional"))
      (node (ref "K1") (pin "10") (pinfunction "S_10") (pintype "passive"))
    )
    (net (code "54") (name "Net-(K2A-1)") (class "Default")
      (node (ref "K2") (pin "2") (pinfunction "1_2") (pintype "passive"))
      (node (ref "Q4") (pin "3") (pinfunction "D_3") (pintype "passive"))
    )
    (net (code "55") (name "Net-(K2B-S)") (class "Default")
      (node (ref "J2") (pin "6") (pinfunction "6_6") (pintype "bidirectional"))
      (node (ref "K2") (pin "10") (pinfunction "S_10") (pintype "passive"))
    )
    (net (code "56") (name "Net-(LED1-PadA)") (class "Default")
      (node (ref "LED1") (pin "A") (pinfunction "A_A") (pintype "passive"))
      (node (ref "R17") (pin "2") (pinfunction "2_2") (pintype "passive"))
    )
    (net (code "57") (name "Net-(LED2-PadA)") (class "Default")
      (node (ref "LED2") (pin "A") (pinfunction "A_A") (pintype "passive"))
      (node (ref "R19") (pin "1") (pinfunction "1_1") (pintype "passive"))
    )
    (net (code "58") (name "Net-(POWER-NO_2)") (class "Default")
      (node (ref "D2") (pin "A") (pinfunction "A_A") (pintype "passive"))
      (node (ref "POWER") (pin "4") (pinfunction "NO_2_4") (pintype "bidirectional"))
      (node (ref "Q3") (pin "3") (pinfunction "D_3") (pintype "passive"))
    )
    (net (code "59") (name "Net-(R13-Pad1)") (class "Default")
      (node (ref "R13") (pin "1") (pinfunction "1_1") (pintype "passive"))
      (node (ref "R6") (pin "1") (pinfunction "1_1") (pintype "passive"))
    )
    (net (code "60") (name "Net-(R13-Pad2)") (class "Default")
      (node (ref "R13") (pin "2") (pinfunction "2_2") (pintype "passive"))
      (node (ref "R14") (pin "2") (pinfunction "2_2") (pintype "passive"))
    )
    (net (code "61") (name "Net-(R_FTDIB-1)") (class "Default")
      (node (ref "R_FTDI") (pin "2") (pinfunction "1_2") (pintype "passive"))
      (node (ref "U1") (pin "31") (pinfunction "PD1(TXD/PCINT17)_31") (pintype "bidirectional"))
    )
    (net (code "62") (name "Net-(R_FTDIC-1)") (class "Default")
      (node (ref "R_FTDI") (pin "3") (pinfunction "1_3") (pintype "passive"))
      (node (ref "U1") (pin "30") (pinfunction "PD0(RXD/PCINT16)_30") (pintype "bidirectional"))
    )
    (net (code "63") (name "Net-(S1-COM_2)") (class "Default")
      (node (ref "S1") (pin "2") (pinfunction "COM_2_2") (pintype "bidirectional"))
      (node (ref "U1") (pin "1") (pinfunction "PD3(PCINT19/OC2B/INT1)_1") (pintype "bidirectional"))
    )
    (net (code "64") (name "Net-(S2-COM_1)") (class "Default")
      (node (ref "S2") (pin "1") (pinfunction "COM_1_1") (pintype "bidirectional"))
      (node (ref "U1") (pin "32") (pinfunction "PD2(INT0/PCINT18)_32") (pintype "bidirectional"))
    )
    (net (code "65") (name "Net-(U1-(PCINT6{slash}XTAL1{slash}TOSC1)PB6)") (class "Default")
      (node (ref "R20") (pin "2") (pinfunction "2_2") (pintype "passive"))
      (node (ref "U1") (pin "7") (pinfunction "(PCINT6/XTAL1/TOSC1)PB6_7") (pintype "bidirectional"))
      (node (ref "Y2") (pin "1") (pinfunction "1_1") (pintype "passive"))
    )
    (net (code "66") (name "Net-(U1-(PCINT7{slash}XTAL2{slash}TOSC2)PB7)") (class "Default")
      (node (ref "R20") (pin "1") (pinfunction "1_1") (pintype "passive"))
      (node (ref "U1") (pin "8") (pinfunction "(PCINT7/XTAL2/TOSC2)PB7_8") (pintype "bidirectional"))
      (node (ref "Y2") (pin "3") (pinfunction "3_3") (pintype "passive"))
    )
    (net (code "67") (name "Net-(U1-(RESET{slash}PCINT14)PC6)") (class "Default")
      (node (ref "C23") (pin "1") (pinfunction "1_1") (pintype "passive"))
      (node (ref "R21") (pin "1") (pinfunction "1_1") (pintype "passive"))
      (node (ref "R_RESET") (pin "2") (pinfunction "2_2") (pintype "passive"))
      (node (ref "U1") (pin "29") (pinfunction "(RESET/PCINT14)PC6_29") (pintype "bidirectional"))
    )
    (net (code "68") (name "Net-(U1-AREF)") (class "Default")
      (node (ref "C22") (pin "1") (pinfunction "1_1") (pintype "passive"))
      (node (ref "U1") (pin "20") (pinfunction "AREF_20") (pintype "power_in"))
    )
    (net (code "69") (name "Net-(U2-(ADC5{slash}SCL{slash}PCINT13)PC5)") (class "Default")
      (node (ref "I2C") (pin "1") (pinfunction "1_1") (pintype "passive"))
      (node (ref "R10") (pin "1") (pinfunction "1_1") (pintype "passive"))
      (node (ref "U2") (pin "28") (pinfunction "(ADC5/SCL/PCINT13)PC5_28") (pintype "bidirectional"))
    )
    (net (code "70") (name "Net-(U2-(PCINT6{slash}XTAL1{slash}TOSC1)PB6)") (class "Default")
      (node (ref "R7") (pin "2") (pinfunction "2_2") (pintype "passive"))
      (node (ref "U2") (pin "7") (pinfunction "(PCINT6/XTAL1/TOSC1)PB6_7") (pintype "bidirectional"))
      (node (ref "Y1") (pin "1") (pinfunction "1_1") (pintype "passive"))
    )
    (net (code "71") (name "Net-(U2-(PCINT7{slash}XTAL2{slash}TOSC2)PB7)") (class "Default")
      (node (ref "R7") (pin "1") (pinfunction "1_1") (pintype "passive"))
      (node (ref "U2") (pin "8") (pinfunction "(PCINT7/XTAL2/TOSC2)PB7_8") (pintype "bidirectional"))
      (node (ref "Y1") (pin "3") (pinfunction "3_3") (pintype "passive"))
    )
    (net (code "72") (name "Net-(U2-AREF)") (class "Default")
      (node (ref "C1") (pin "1") (pinfunction "1_1") (pintype "passive"))
      (node (ref "U2") (pin "20") (pinfunction "AREF_20") (pintype "power_in"))
    )
    (net (code "73") (name "Net-(U2-PD0(RXD{slash}PCINT16))") (class "Default")
      (node (ref "R2") (pin "1") (pinfunction "1_1") (pintype "passive"))
      (node (ref "U2") (pin "30") (pinfunction "PD0(RXD/PCINT16)_30") (pintype "bidirectional"))
    )
    (net (code "74") (name "Net-(U2-PD1(TXD{slash}PCINT17))") (class "Default")
      (node (ref "R1") (pin "1") (pinfunction "1_1") (pintype "passive"))
      (node (ref "U2") (pin "31") (pinfunction "PD1(TXD/PCINT17)_31") (pintype "bidirectional"))
    )
    (net (code "75") (name "RESET") (class "Default")
      (node (ref "C20") (pin "1") (pinfunction "1_1") (pintype "passive"))
      (node (ref "JP1") (pin "5") (pinfunction "5_5") (pintype "passive"))
      (node (ref "R12") (pin "1") (pinfunction "1_1") (pintype "passive"))
      (node (ref "RESET") (pin "4") (pinfunction "NO_2_4") (pintype "bidirectional"))
      (node (ref "U2") (pin "29") (pinfunction "(RESET/PCINT14)PC6_29") (pintype "bidirectional"))
    )
    (net (code "76") (name "SCK") (class "Default")
      (node (ref "IC3") (pin "3") (pinfunction "SCK_3") (pintype "bidirectional"))
      (node (ref "JP1") (pin "3") (pinfunction "3_3") (pintype "passive"))
      (node (ref "JP8") (pin "5") (pinfunction "5_5") (pintype "passive"))
      (node (ref "U2") (pin "17") (pinfunction "(SCK/PCINT5)PB5_17") (pintype "bidirectional"))
    )
    (net (code "77") (name "S_LOCK") (class "Default")
      (node (ref "Q2") (pin "1") (pinfunction "G_1") (pintype "passive"))
      (node (ref "R18") (pin "2") (pinfunction "2_2") (pintype "passive"))
      (node (ref "R19") (pin "2") (pinfunction "2_2") (pintype "passive"))
      (node (ref "U2") (pin "10") (pinfunction "PD6(PCINT22/OC0A/AIN0)_10") (pintype "bidirectional"))
    )
    (net (code "78") (name "S_POWER") (class "Default")
      (node (ref "Q3") (pin "1") (pinfunction "G_1") (pintype "passive"))
      (node (ref "R3") (pin "2") (pinfunction "2_2") (pintype "passive"))
      (node (ref "U2") (pin "9") (pinfunction "PD5(PCINT21/OC0B/T1)_9") (pintype "bidirectional"))
    )
    (net (code "79") (name "S_UNLOCK") (class "Default")
      (node (ref "Q4") (pin "1") (pinfunction "G_1") (pintype "passive"))
      (node (ref "R16") (pin "1") (pinfunction "1_1") (pintype "passive"))
      (node (ref "R17") (pin "1") (pinfunction "1_1") (pintype "passive"))
      (node (ref "U2") (pin "11") (pinfunction "PD7(PCINT23/AIN1)_11") (pintype "bidirectional"))
    )
    (net (code "80") (name "VCC") (class "Default")
      (node (ref "C14") (pin "1") (pinfunction "1_1") (pintype "passive"))
      (node (ref "C15") (pin "1") (pinfunction "1_1") (pintype "passive"))
      (node (ref "C19") (pin "1") (pinfunction "1_1") (pintype "passive"))
      (node (ref "C2") (pin "1") (pinfunction "1_1") (pintype "passive"))
      (node (ref "C6") (pin "2") (pinfunction "2_2") (pintype "passive"))
      (node (ref "C7") (pin "1") (pinfunction "1_1") (pintype "passive"))
      (node (ref "C8") (pin "1") (pinfunction "1_1") (pintype "passive"))
      (node (ref "IC1") (pin "16") (pinfunction "VCC_16") (pintype "bidirectional"))
      (node (ref "IC3") (pin "15") (pinfunction "VDD_2_15") (pintype "bidirectional"))
      (node (ref "IC3") (pin "18") (pinfunction "VDD_3_18") (pintype "bidirectional"))
      (node (ref "IC3") (pin "7") (pinfunction "VDD_1_7") (pintype "bidirectional"))
      (node (ref "JP1") (pin "2") (pinfunction "2_2") (pintype "passive"))
      (node (ref "JP8") (pin "2") (pinfunction "2_2") (pintype "passive"))
      (node (ref "L4") (pin "2") (pinfunction "2_2") (pintype "bidirectional"))
      (node (ref "R10") (pin "2") (pinfunction "2_2") (pintype "passive"))
      (node (ref "R11") (pin "2") (pinfunction "2_2") (pintype "passive"))
      (node (ref "R12") (pin "2") (pinfunction "2_2") (pintype "passive"))
      (node (ref "R6") (pin "2") (pinfunction "2_2") (pintype "passive"))
      (node (ref "TP3") (pin "TP") (pinfunction "TP_TP") (pintype "input"))
      (node (ref "U2") (pin "18") (pinfunction "AVCC_18") (pintype "power_in"))
      (node (ref "U2") (pin "4") (pinfunction "VCC_4") (pintype "power_in"))
      (node (ref "U2") (pin "6") (pinfunction "VCC1_6") (pintype "power_in"))
    )
    (net (code "81") (name "VCC{slash}2") (class "Default")
      (node (ref "B1") (pin "+$1") (pinfunction "+_+$1") (pintype "passive"))
      (node (ref "B1") (pin "+$2") (pinfunction "+_+$2") (pintype "passive"))
      (node (ref "B2") (pin "+$1") (pinfunction "+_+$1") (pintype "passive"))
      (node (ref "B2") (pin "+$2") (pinfunction "+_+$2") (pintype "passive"))
      (node (ref "C29") (pin "1") (pinfunction "1_1") (pintype "passive"))
      (node (ref "C30") (pin "1") (pinfunction "1_1") (pintype "passive"))
      (node (ref "IC2") (pin "15") (pinfunction "VDD_2_15") (pintype "bidirectional"))
      (node (ref "IC2") (pin "18") (pinfunction "VDD_3_18") (pintype "bidirectional"))
      (node (ref "IC2") (pin "7") (pinfunction "VDD_1_7") (pintype "bidirectional"))
      (node (ref "R21") (pin "2") (pinfunction "2_2") (pintype "passive"))
      (node (ref "R_FTDI") (pin "4") (pinfunction "1_4") (pintype "passive"))
      (node (ref "U1") (pin "18") (pinfunction "AVCC_18") (pintype "power_in"))
      (node (ref "U1") (pin "23") (pinfunction "(ADC0/PCINT8)PC0_23") (pintype "bidirectional"))
      (node (ref "U1") (pin "4") (pinfunction "VCC_4") (pintype "power_in"))
      (node (ref "U1") (pin "6") (pinfunction "VCC1_6") (pintype "power_in"))
    )
    (net (code "82") (name "V_SENSE") (class "Default")
      (node (ref "R4") (pin "1") (pinfunction "1_1") (pintype "passive"))
      (node (ref "R5") (pin "2") (pinfunction "2_2") (pintype "passive"))
      (node (ref "U2") (pin "23") (pinfunction "(ADC0/PCINT8)PC0_23") (pintype "bidirectional"))
    )
    (net (code "83") (name "unconnected-(ANT1-NC-Pad2)") (class "Default")
      (node (ref "ANT1") (pin "2") (pinfunction "NC_2") (pintype "no_connect"))
    )
    (net (code "84") (name "unconnected-(IC1-DIN2-Pad10)") (class "Default")
      (node (ref "IC1") (pin "10") (pinfunction "DIN2_10") (pintype "bidirectional"))
    )
    (net (code "85") (name "unconnected-(IC1-DOUT2-Pad7)") (class "Default")
      (node (ref "IC1") (pin "7") (pinfunction "DOUT2_7") (pintype "bidirectional"))
    )
    (net (code "86") (name "unconnected-(IC1-RIN2-Pad8)") (class "Default")
      (node (ref "IC1") (pin "8") (pinfunction "RIN2_8") (pintype "bidirectional"))
    )
    (net (code "87") (name "unconnected-(IC1-ROUT2-Pad9)") (class "Default")
      (node (ref "IC1") (pin "9") (pinfunction "ROUT2_9") (pintype "bidirectional"))
    )
    (net (code "88") (name "unconnected-(IC2-IRQ-Pad6)") (class "Default")
      (node (ref "IC2") (pin "6") (pinfunction "IRQ_6") (pintype "bidirectional"))
    )
    (net (code "89") (name "unconnected-(IC2-THERMAL_PAD-Pad21)") (class "Default")
      (node (ref "IC2") (pin "21") (pinfunction "THERMAL_PAD_21") (pintype "bidirectional"))
    )
    (net (code "90") (name "unconnected-(IC3-THERMAL_PAD-Pad21)") (class "Default")
      (node (ref "IC3") (pin "21") (pinfunction "THERMAL_PAD_21") (pintype "bidirectional"))
    )
    (net (code "91") (name "unconnected-(J2-Pad4)") (class "Default")
      (node (ref "J2") (pin "4") (pinfunction "4_4") (pintype "bidirectional"))
    )
    (net (code "92") (name "unconnected-(K1B-O-Pad1)") (class "Default")
      (node (ref "K1") (pin "1") (pinfunction "O_1") (pintype "passive"))
    )
    (net (code "93") (name "unconnected-(K2B-O-Pad1)") (class "Default")
      (node (ref "K2") (pin "1") (pinfunction "O_1") (pintype "passive"))
    )
    (net (code "94") (name "unconnected-(POWER-COM_1-Pad1)") (class "Default")
      (node (ref "POWER") (pin "1") (pinfunction "COM_1_1") (pintype "bidirectional"))
    )
    (net (code "95") (name "unconnected-(POWER-NO_1-Pad3)") (class "Default")
      (node (ref "POWER") (pin "3") (pinfunction "NO_1_3") (pintype "bidirectional"))
    )
    (net (code "96") (name "unconnected-(RESET-COM_1-Pad1)") (class "Default")
      (node (ref "RESET") (pin "1") (pinfunction "COM_1_1") (pintype "bidirectional"))
    )
    (net (code "97") (name "unconnected-(RESET-NO_1-Pad3)") (class "Default")
      (node (ref "RESET") (pin "3") (pinfunction "NO_1_3") (pintype "bidirectional"))
    )
    (net (code "98") (name "unconnected-(S1-COM_1-Pad1)") (class "Default")
      (node (ref "S1") (pin "1") (pinfunction "COM_1_1") (pintype "bidirectional"))
    )
    (net (code "99") (name "unconnected-(S1-NO_1-Pad3)") (class "Default")
      (node (ref "S1") (pin "3") (pinfunction "NO_1_3") (pintype "bidirectional"))
    )
    (net (code "100") (name "unconnected-(S2-COM_2-Pad2)") (class "Default")
      (node (ref "S2") (pin "2") (pinfunction "COM_2_2") (pintype "bidirectional"))
    )
    (net (code "101") (name "unconnected-(S2-NO_2-Pad4)") (class "Default")
      (node (ref "S2") (pin "4") (pinfunction "NO_2_4") (pintype "bidirectional"))
    )
    (net (code "102") (name "unconnected-(U1-(ADC1{slash}PCINT9)PC1-Pad24)") (class "Default")
      (node (ref "U1") (pin "24") (pinfunction "(ADC1/PCINT9)PC1_24") (pintype "bidirectional"))
    )
    (net (code "103") (name "unconnected-(U1-(ADC2{slash}PCINT10)PC2-Pad25)") (class "Default")
      (node (ref "U1") (pin "25") (pinfunction "(ADC2/PCINT10)PC2_25") (pintype "bidirectional"))
    )
    (net (code "104") (name "unconnected-(U1-(ADC3{slash}PCINT11)PC3-Pad26)") (class "Default")
      (node (ref "U1") (pin "26") (pinfunction "(ADC3/PCINT11)PC3_26") (pintype "bidirectional"))
    )
    (net (code "105") (name "unconnected-(U1-(ADC4{slash}SDA{slash}PCINT12)PC4-Pad27)") (class "Default")
      (node (ref "U1") (pin "27") (pinfunction "(ADC4/SDA/PCINT12)PC4_27") (pintype "bidirectional"))
    )
    (net (code "106") (name "unconnected-(U1-(ADC5{slash}SCL{slash}PCINT13)PC5-Pad28)") (class "Default")
      (node (ref "U1") (pin "28") (pinfunction "(ADC5/SCL/PCINT13)PC5_28") (pintype "bidirectional"))
    )
    (net (code "107") (name "unconnected-(U1-(PCINT2{slash}SS{slash}OC1B)PB2-Pad14)") (class "Default")
      (node (ref "U1") (pin "14") (pinfunction "(PCINT2/SS/OC1B)PB2_14") (pintype "bidirectional"))
    )
    (net (code "108") (name "unconnected-(U1-ADC6-Pad19)") (class "Default")
      (node (ref "U1") (pin "19") (pinfunction "ADC6_19") (pintype "input"))
    )
    (net (code "109") (name "unconnected-(U1-ADC7-Pad22)") (class "Default")
      (node (ref "U1") (pin "22") (pinfunction "ADC7_22") (pintype "input"))
    )
    (net (code "110") (name "unconnected-(U1-PD4(PCINT20{slash}XCK{slash}T0)-Pad2)") (class "Default")
      (node (ref "U1") (pin "2") (pinfunction "PD4(PCINT20/XCK/T0)_2") (pintype "bidirectional"))
    )
    (net (code "111") (name "unconnected-(U1-PD5(PCINT21{slash}OC0B{slash}T1)-Pad9)") (class "Default")
      (node (ref "U1") (pin "9") (pinfunction "PD5(PCINT21/OC0B/T1)_9") (pintype "bidirectional"))
    )
    (net (code "112") (name "unconnected-(U1-PD6(PCINT22{slash}OC0A{slash}AIN0)-Pad10)") (class "Default")
      (node (ref "U1") (pin "10") (pinfunction "PD6(PCINT22/OC0A/AIN0)_10") (pintype "bidirectional"))
    )
    (net (code "113") (name "unconnected-(U1-PD7(PCINT23{slash}AIN1)-Pad11)") (class "Default")
      (node (ref "U1") (pin "11") (pinfunction "PD7(PCINT23/AIN1)_11") (pintype "bidirectional"))
    )
    (net (code "114") (name "unconnected-(U2-(ADC1{slash}PCINT9)PC1-Pad24)") (class "Default")
      (node (ref "U2") (pin "24") (pinfunction "(ADC1/PCINT9)PC1_24") (pintype "bidirectional"))
    )
    (net (code "115") (name "unconnected-(U2-(ADC2{slash}PCINT10)PC2-Pad25)") (class "Default")
      (node (ref "U2") (pin "25") (pinfunction "(ADC2/PCINT10)PC2_25") (pintype "bidirectional"))
    )
    (net (code "116") (name "unconnected-(U2-(ADC3{slash}PCINT11)PC3-Pad26)") (class "Default")
      (node (ref "U2") (pin "26") (pinfunction "(ADC3/PCINT11)PC3_26") (pintype "bidirectional"))
    )
    (net (code "117") (name "unconnected-(U2-(PCINT2{slash}SS{slash}OC1B)PB2-Pad14)") (class "Default")
      (node (ref "U2") (pin "14") (pinfunction "(PCINT2/SS/OC1B)PB2_14") (pintype "bidirectional"))
    )
    (net (code "118") (name "unconnected-(U2-ADC6-Pad19)") (class "Default")
      (node (ref "U2") (pin "19") (pinfunction "ADC6_19") (pintype "input"))
    )
    (net (code "119") (name "unconnected-(U2-ADC7-Pad22)") (class "Default")
      (node (ref "U2") (pin "22") (pinfunction "ADC7_22") (pintype "input"))
    )
    (net (code "120") (name "unconnected-(U2-PD3(PCINT19{slash}OC2B{slash}INT1)-Pad1)") (class "Default")
      (node (ref "U2") (pin "1") (pinfunction "PD3(PCINT19/OC2B/INT1)_1") (pintype "bidirectional"))
    )
    (net (code "121") (name "unconnected-(U2-PD4(PCINT20{slash}XCK{slash}T0)-Pad2)") (class "Default")
      (node (ref "U2") (pin "2") (pinfunction "PD4(PCINT20/XCK/T0)_2") (pintype "bidirectional"))
    )
    (net (code "122") (name "unconnected-(X1A-KL-Pad1)") (class "Default")
      (node (ref "X1") (pin "1") (pinfunction "KL_1") (pintype "passive"))
    )
    (net (code "123") (name "unconnected-(X1B-KL-Pad10)") (class "Default")
      (node (ref "X1") (pin "10") (pinfunction "KL_10") (pintype "passive"))
    )
    (net (code "124") (name "unconnected-(X1E-KL-Pad4)") (class "Default")
      (node (ref "X1") (pin "4") (pinfunction "KL_4") (pintype "passive"))
    )
    (net (code "125") (name "unconnected-(X1G-KL-Pad6)") (class "Default")
      (node (ref "X1") (pin "6") (pinfunction "KL_6") (pintype "passive"))
    )
    (net (code "126") (name "unconnected-(X1H-KL-Pad7)") (class "Default")
      (node (ref "X1") (pin "7") (pinfunction "KL_7") (pintype "passive"))
    )
    (net (code "127") (name "unconnected-(X1I-KL-Pad8)") (class "Default")
      (node (ref "X1") (pin "8") (pinfunction "KL_8") (pintype "passive"))
    )
    (net (code "128") (name "unconnected-(X1J-KL-Pad9)") (class "Default")
      (node (ref "X1") (pin "9") (pinfunction "KL_9") (pintype "passive"))
    )
  )
)
